# 1_1_5_Interface_board_Servos.net
KiCad netlist of a schematic drawn in Altium Designer
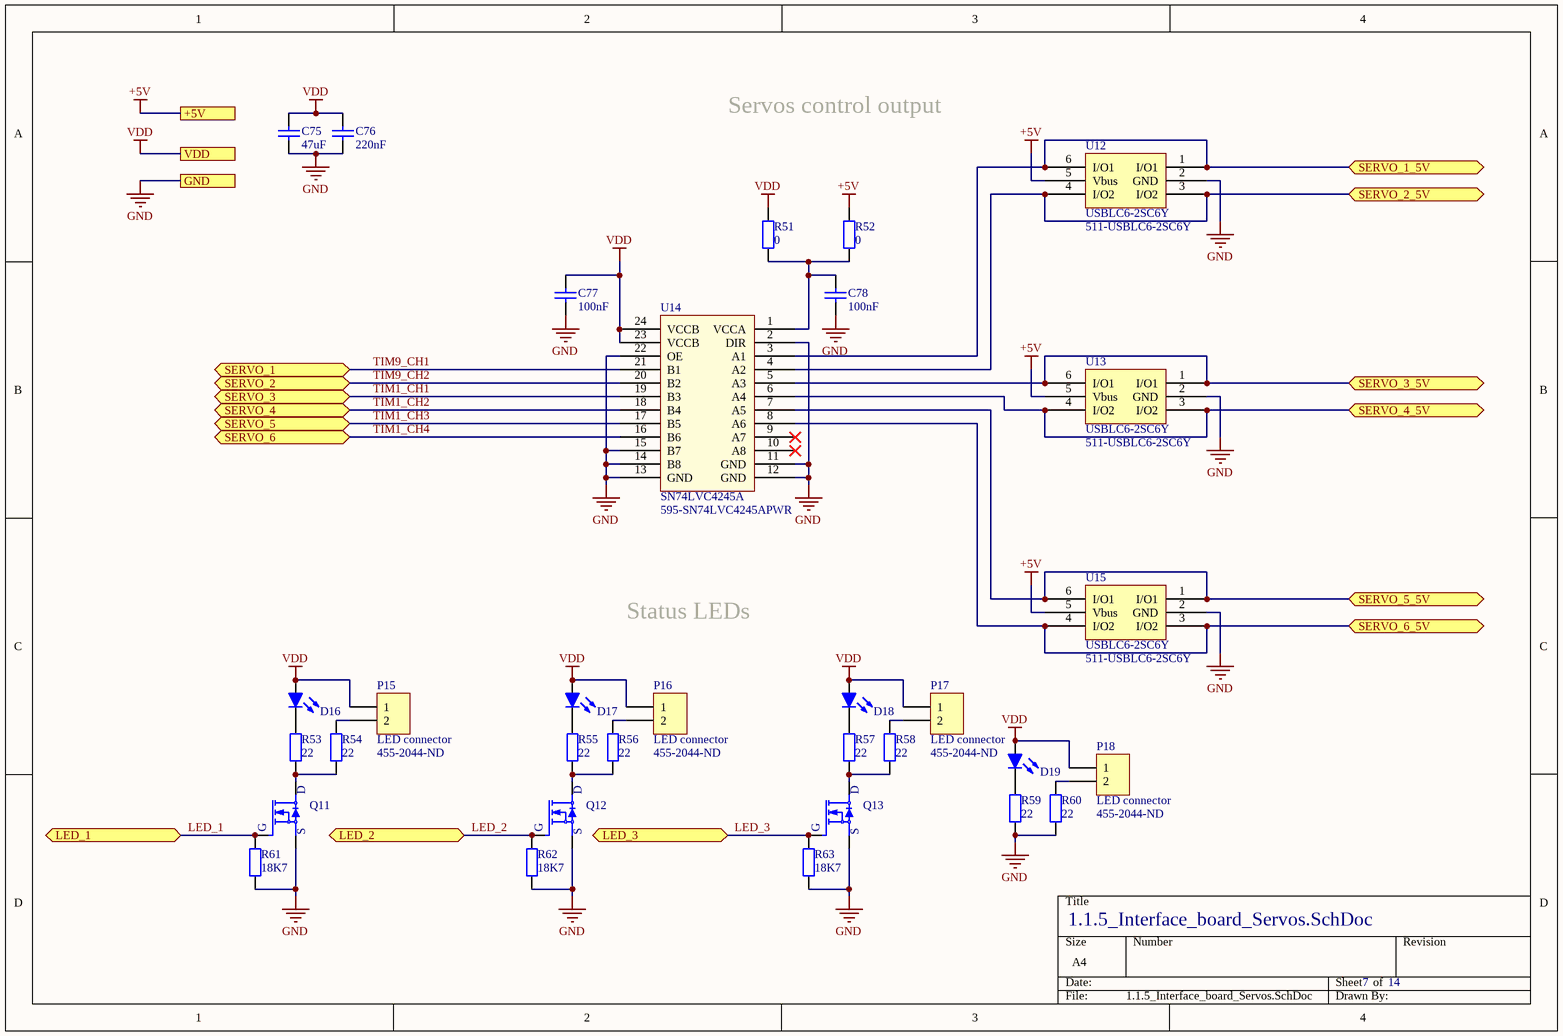
[diagram p0: 1.1.5_Interface_board_Servos.SchDoc]

(export (version "E")
  (design (tool "Eeschema 10.0.6"))
  (components
    (comp (ref "C75")
      (value "47uF")
      (footprint "CAP1206W")
      (description "Capacitor")
      (libsource (lib "Rocket_library") (part "C_47uF_25v_1206"))
    )
    (comp (ref "C76")
      (value "220nF")
      (footprint "CAP0603R")
      (description "Capacitor")
      (libsource (lib "Rocket_library") (part "C_220nF"))
    )
    (comp (ref "C77")
      (value "100nF")
      (footprint "CAP0603R")
      (description "Capacitor")
      (libsource (lib "Rocket_library") (part "C_100nF"))
    )
    (comp (ref "C78")
      (value "100nF")
      (footprint "CAP0603R")
      (description "Capacitor")
      (libsource (lib "Rocket_library") (part "C_100nF"))
    )
    (comp (ref "D16")
      (value "LED")
      (footprint "WL-SMCW")
      (description "Standard LEDs - SMD WL-SMCW Waterclr 0603 Green")
      (libsource (lib "Rocket_library") (part "LED_SMD_GREEN_0603"))
    )
    (comp (ref "D17")
      (value "LED")
      (footprint "WL-SMCW")
      (description "Standard LEDs - SMD WL-SMCW Waterclr 0603 Green")
      (libsource (lib "Rocket_library") (part "LED_SMD_GREEN_0603"))
    )
    (comp (ref "D18")
      (value "LED")
      (footprint "WL-SMCW")
      (description "Standard LEDs - SMD WL-SMCW Waterclr 0603 Green")
      (libsource (lib "Rocket_library") (part "LED_SMD_GREEN_0603"))
    )
    (comp (ref "D19")
      (value "LED")
      (footprint "WL-SMCW")
      (description "Standard LEDs - SMD WL-SMCW Waterclr 0603 Green")
      (libsource (lib "Rocket_library") (part "LED_SMD_GREEN_0603"))
    )
    (comp (ref "P15")
      (value "LED connector")
      (footprint "CON_JST_XA_ S02B-XASS-1")
      (description "Header 2p JST XA 3A right angle")
      (fields (field (name "SUPPLIER PART NUMBER 1") "455-2044-ND"))
      (libsource (lib "Rocket_library") (part "Header 2p JST XA 3A right angle"))
    )
    (comp (ref "P16")
      (value "LED connector")
      (footprint "CON_JST_XA_ S02B-XASS-1")
      (description "Header 2p JST XA 3A right angle")
      (fields (field (name "SUPPLIER PART NUMBER 1") "455-2044-ND"))
      (libsource (lib "Rocket_library") (part "Header 2p JST XA 3A right angle"))
    )
    (comp (ref "P17")
      (value "LED connector")
      (footprint "CON_JST_XA_ S02B-XASS-1")
      (description "Header 2p JST XA 3A right angle")
      (fields (field (name "SUPPLIER PART NUMBER 1") "455-2044-ND"))
      (libsource (lib "Rocket_library") (part "Header 2p JST XA 3A right angle"))
    )
    (comp (ref "P18")
      (value "LED connector")
      (footprint "CON_JST_XA_ S02B-XASS-1")
      (description "Header 2p JST XA 3A right angle")
      (fields (field (name "SUPPLIER PART NUMBER 1") "455-2044-ND"))
      (libsource (lib "Rocket_library") (part "Header 2p JST XA 3A right angle"))
    )
    (comp (ref "Q11")
      (value "MOSFET_N")
      (footprint "SOT-323-3")
      (description "MOSFET N-Ch 20V 1.4A SOT-323-3")
      (libsource (lib "Rocket_library") (part "MOSFET_N_ 20V_1.4A"))
    )
    (comp (ref "Q12")
      (value "MOSFET_N")
      (footprint "SOT-323-3")
      (description "MOSFET N-Ch 20V 1.4A SOT-323-3")
      (libsource (lib "Rocket_library") (part "MOSFET_N_ 20V_1.4A"))
    )
    (comp (ref "Q13")
      (value "MOSFET_N")
      (footprint "SOT-323-3")
      (description "MOSFET N-Ch 20V 1.4A SOT-323-3")
      (libsource (lib "Rocket_library") (part "MOSFET_N_ 20V_1.4A"))
    )
    (comp (ref "R51")
      (value "0")
      (footprint "0603")
      (description "0 Ohm")
      (libsource (lib "Rocket_library") (part "R_0603_0Ohm_jumper"))
    )
    (comp (ref "R52")
      (value "0")
      (footprint "0603")
      (description "0 Ohm")
      (libsource (lib "Rocket_library") (part "R_0603_0Ohm_jumper"))
    )
    (comp (ref "R53")
      (value "22")
      (footprint "0603")
      (description "0.25W 22Ohm")
      (libsource (lib "Rocket_library") (part "R_0603_025W_22Ohm"))
    )
    (comp (ref "R54")
      (value "22")
      (footprint "0603")
      (description "0.25W 22Ohm")
      (libsource (lib "Rocket_library") (part "R_0603_025W_22Ohm"))
    )
    (comp (ref "R55")
      (value "22")
      (footprint "0603")
      (description "0.25W 22Ohm")
      (libsource (lib "Rocket_library") (part "R_0603_025W_22Ohm"))
    )
    (comp (ref "R56")
      (value "22")
      (footprint "0603")
      (description "0.25W 22Ohm")
      (libsource (lib "Rocket_library") (part "R_0603_025W_22Ohm"))
    )
    (comp (ref "R57")
      (value "22")
      (footprint "0603")
      (description "0.25W 22Ohm")
      (libsource (lib "Rocket_library") (part "R_0603_025W_22Ohm"))
    )
    (comp (ref "R58")
      (value "22")
      (footprint "0603")
      (description "0.25W 22Ohm")
      (libsource (lib "Rocket_library") (part "R_0603_025W_22Ohm"))
    )
    (comp (ref "R59")
      (value "22")
      (footprint "0603")
      (description "0.25W 22Ohm")
      (libsource (lib "Rocket_library") (part "R_0603_025W_22Ohm"))
    )
    (comp (ref "R60")
      (value "22")
      (footprint "0603")
      (description "0.25W 22Ohm")
      (libsource (lib "Rocket_library") (part "R_0603_025W_22Ohm"))
    )
    (comp (ref "R61")
      (value "18K7")
      (footprint "0603")
      (description "0.1W 18K7")
      (libsource (lib "Rocket_library") (part "R_0603_01W_18K7"))
    )
    (comp (ref "R62")
      (value "18K7")
      (footprint "0603")
      (description "0.1W 18K7")
      (libsource (lib "Rocket_library") (part "R_0603_01W_18K7"))
    )
    (comp (ref "R63")
      (value "18K7")
      (footprint "0603")
      (description "0.1W 18K7")
      (libsource (lib "Rocket_library") (part "R_0603_01W_18K7"))
    )
    (comp (ref "U12")
      (value "USBLC6-2SC6Y")
      (footprint "SOT23-6L")
      (description "ESD Suppressors")
      (fields (field (name "SUPPLIER PART NUMBER 1") "511-USBLC6-2SC6Y"))
      (libsource (lib "Rocket_library") (part "USBLC6-2SC6Y"))
    )
    (comp (ref "U13")
      (value "USBLC6-2SC6Y")
      (footprint "SOT23-6L")
      (description "ESD Suppressors")
      (fields (field (name "SUPPLIER PART NUMBER 1") "511-USBLC6-2SC6Y"))
      (libsource (lib "Rocket_library") (part "USBLC6-2SC6Y"))
    )
    (comp (ref "U14")
      (value "SN74LVC4245A")
      (footprint "TSSOP 24")
      (description "Level shifter 8")
      (fields (field (name "SUPPLIER PART NUMBER 1") "595-SN74LVC4245APWR"))
      (libsource (lib "Rocket_library") (part "SN74LVC4245A"))
    )
    (comp (ref "U15")
      (value "USBLC6-2SC6Y")
      (footprint "SOT23-6L")
      (description "ESD Suppressors")
      (fields (field (name "SUPPLIER PART NUMBER 1") "511-USBLC6-2SC6Y"))
      (libsource (lib "Rocket_library") (part "USBLC6-2SC6Y"))
    )
  )
  (nets
    (net (code "1") (name "+5V") (class "Default")
      (node (ref "R52") (pin "2") (pinfunction "2_2") (pintype "passive"))
      (node (ref "U12") (pin "5") (pinfunction "Vbus_5") (pintype "passive"))
      (node (ref "U13") (pin "5") (pinfunction "Vbus_5") (pintype "passive"))
      (node (ref "U15") (pin "5") (pinfunction "Vbus_5") (pintype "passive"))
    )
    (net (code "2") (name "/LED_1") (class "Default")
      (node (ref "Q11") (pin "1") (pinfunction "G_1") (pintype "passive"))
      (node (ref "R61") (pin "2") (pinfunction "2_2") (pintype "passive"))
    )
    (net (code "3") (name "/LED_2") (class "Default")
      (node (ref "Q12") (pin "1") (pinfunction "G_1") (pintype "passive"))
      (node (ref "R62") (pin "2") (pinfunction "2_2") (pintype "passive"))
    )
    (net (code "4") (name "/LED_3") (class "Default")
      (node (ref "Q13") (pin "1") (pinfunction "G_1") (pintype "passive"))
      (node (ref "R63") (pin "2") (pinfunction "2_2") (pintype "passive"))
    )
    (net (code "5") (name "/SERVO_1_5V") (class "Default")
      (node (ref "U12") (pin "1") (pinfunction "I/O1_1") (pintype "passive"))
      (node (ref "U12") (pin "6") (pinfunction "I/O1_6") (pintype "passive"))
      (node (ref "U14") (pin "3") (pinfunction "A1_3") (pintype "passive"))
    )
    (net (code "6") (name "/SERVO_2_5V") (class "Default")
      (node (ref "U12") (pin "3") (pinfunction "I/O2_3") (pintype "passive"))
      (node (ref "U12") (pin "4") (pinfunction "I/O2_4") (pintype "passive"))
      (node (ref "U14") (pin "4") (pinfunction "A2_4") (pintype "passive"))
    )
    (net (code "7") (name "/SERVO_3_5V") (class "Default")
      (node (ref "U13") (pin "1") (pinfunction "I/O1_1") (pintype "passive"))
      (node (ref "U13") (pin "6") (pinfunction "I/O1_6") (pintype "passive"))
      (node (ref "U14") (pin "5") (pinfunction "A3_5") (pintype "passive"))
    )
    (net (code "8") (name "/SERVO_4_5V") (class "Default")
      (node (ref "U13") (pin "3") (pinfunction "I/O2_3") (pintype "passive"))
      (node (ref "U13") (pin "4") (pinfunction "I/O2_4") (pintype "passive"))
      (node (ref "U14") (pin "6") (pinfunction "A4_6") (pintype "passive"))
    )
    (net (code "9") (name "/SERVO_5_5V") (class "Default")
      (node (ref "U14") (pin "7") (pinfunction "A5_7") (pintype "passive"))
      (node (ref "U15") (pin "1") (pinfunction "I/O1_1") (pintype "passive"))
      (node (ref "U15") (pin "6") (pinfunction "I/O1_6") (pintype "passive"))
    )
    (net (code "10") (name "/SERVO_6_5V") (class "Default")
      (node (ref "U14") (pin "8") (pinfunction "A6_8") (pintype "passive"))
      (node (ref "U15") (pin "3") (pinfunction "I/O2_3") (pintype "passive"))
      (node (ref "U15") (pin "4") (pinfunction "I/O2_4") (pintype "passive"))
    )
    (net (code "11") (name "/TIM1_CH1") (class "Default")
      (node (ref "U14") (pin "19") (pinfunction "B3_19") (pintype "passive"))
    )
    (net (code "12") (name "/TIM1_CH2") (class "Default")
      (node (ref "U14") (pin "18") (pinfunction "B4_18") (pintype "passive"))
    )
    (net (code "13") (name "/TIM1_CH3") (class "Default")
      (node (ref "U14") (pin "17") (pinfunction "B5_17") (pintype "passive"))
    )
    (net (code "14") (name "/TIM1_CH4") (class "Default")
      (node (ref "U14") (pin "16") (pinfunction "B6_16") (pintype "passive"))
    )
    (net (code "15") (name "/TIM9_CH1") (class "Default")
      (node (ref "U14") (pin "21") (pinfunction "B1_21") (pintype "passive"))
    )
    (net (code "16") (name "/TIM9_CH2") (class "Default")
      (node (ref "U14") (pin "20") (pinfunction "B2_20") (pintype "passive"))
    )
    (net (code "17") (name "GND") (class "Default")
      (node (ref "C75") (pin "1") (pinfunction "1_1") (pintype "passive"))
      (node (ref "C76") (pin "1") (pinfunction "1_1") (pintype "passive"))
      (node (ref "C77") (pin "1") (pinfunction "1_1") (pintype "passive"))
      (node (ref "C78") (pin "1") (pinfunction "1_1") (pintype "passive"))
      (node (ref "Q11") (pin "2") (pinfunction "S_2") (pintype "passive"))
      (node (ref "Q12") (pin "2") (pinfunction "S_2") (pintype "passive"))
      (node (ref "Q13") (pin "2") (pinfunction "S_2") (pintype "passive"))
      (node (ref "R59") (pin "1") (pinfunction "1_1") (pintype "passive"))
      (node (ref "R60") (pin "1") (pinfunction "1_1") (pintype "passive"))
      (node (ref "R61") (pin "1") (pinfunction "1_1") (pintype "passive"))
      (node (ref "R62") (pin "1") (pinfunction "1_1") (pintype "passive"))
      (node (ref "R63") (pin "1") (pinfunction "1_1") (pintype "passive"))
      (node (ref "U12") (pin "2") (pinfunction "GND_2") (pintype "passive"))
      (node (ref "U13") (pin "2") (pinfunction "GND_2") (pintype "passive"))
      (node (ref "U14") (pin "11") (pinfunction "GND_11") (pintype "passive"))
      (node (ref "U14") (pin "12") (pinfunction "GND_12") (pintype "passive"))
      (node (ref "U14") (pin "13") (pinfunction "GND_13") (pintype "passive"))
      (node (ref "U14") (pin "14") (pinfunction "B8_14") (pintype "passive"))
      (node (ref "U14") (pin "15") (pinfunction "B7_15") (pintype "passive"))
      (node (ref "U14") (pin "2") (pinfunction "DIR_2") (pintype "passive"))
      (node (ref "U14") (pin "22") (pinfunction "OE_22") (pintype "passive"))
      (node (ref "U15") (pin "2") (pinfunction "GND_2") (pintype "passive"))
    )
    (net (code "18") (name "Net-(D16-PadC)") (class "Default")
      (node (ref "D16") (pin "C") (pinfunction "C_C") (pintype "passive"))
      (node (ref "R53") (pin "2") (pinfunction "2_2") (pintype "passive"))
    )
    (net (code "19") (name "Net-(D17-PadC)") (class "Default")
      (node (ref "D17") (pin "C") (pinfunction "C_C") (pintype "passive"))
      (node (ref "R55") (pin "2") (pinfunction "2_2") (pintype "passive"))
    )
    (net (code "20") (name "Net-(D18-PadC)") (class "Default")
      (node (ref "D18") (pin "C") (pinfunction "C_C") (pintype "passive"))
      (node (ref "R57") (pin "2") (pinfunction "2_2") (pintype "passive"))
    )
    (net (code "21") (name "Net-(D19-PadC)") (class "Default")
      (node (ref "D19") (pin "C") (pinfunction "C_C") (pintype "passive"))
      (node (ref "R59") (pin "2") (pinfunction "2_2") (pintype "passive"))
    )
    (net (code "22") (name "Net-(P15-Pad2)") (class "Default")
      (node (ref "P15") (pin "2") (pinfunction "2_2") (pintype "passive"))
      (node (ref "R54") (pin "2") (pinfunction "2_2") (pintype "passive"))
    )
    (net (code "23") (name "Net-(P16-Pad2)") (class "Default")
      (node (ref "P16") (pin "2") (pinfunction "2_2") (pintype "passive"))
      (node (ref "R56") (pin "2") (pinfunction "2_2") (pintype "passive"))
    )
    (net (code "24") (name "Net-(P17-Pad2)") (class "Default")
      (node (ref "P17") (pin "2") (pinfunction "2_2") (pintype "passive"))
      (node (ref "R58") (pin "2") (pinfunction "2_2") (pintype "passive"))
    )
    (net (code "25") (name "Net-(P18-Pad2)") (class "Default")
      (node (ref "P18") (pin "2") (pinfunction "2_2") (pintype "passive"))
      (node (ref "R60") (pin "2") (pinfunction "2_2") (pintype "passive"))
    )
    (net (code "26") (name "Net-(Q11-D)") (class "Default")
      (node (ref "Q11") (pin "3") (pinfunction "D_3") (pintype "passive"))
      (node (ref "R53") (pin "1") (pinfunction "1_1") (pintype "passive"))
      (node (ref "R54") (pin "1") (pinfunction "1_1") (pintype "passive"))
    )
    (net (code "27") (name "Net-(Q12-D)") (class "Default")
      (node (ref "Q12") (pin "3") (pinfunction "D_3") (pintype "passive"))
      (node (ref "R55") (pin "1") (pinfunction "1_1") (pintype "passive"))
      (node (ref "R56") (pin "1") (pinfunction "1_1") (pintype "passive"))
    )
    (net (code "28") (name "Net-(Q13-D)") (class "Default")
      (node (ref "Q13") (pin "3") (pinfunction "D_3") (pintype "passive"))
      (node (ref "R57") (pin "1") (pinfunction "1_1") (pintype "passive"))
      (node (ref "R58") (pin "1") (pinfunction "1_1") (pintype "passive"))
    )
    (net (code "29") (name "Net-(U14-VCCA)") (class "Default")
      (node (ref "C78") (pin "2") (pinfunction "2_2") (pintype "passive"))
      (node (ref "R51") (pin "1") (pinfunction "1_1") (pintype "passive"))
      (node (ref "R52") (pin "1") (pinfunction "1_1") (pintype "passive"))
      (node (ref "U14") (pin "1") (pinfunction "VCCA_1") (pintype "passive"))
    )
    (net (code "30") (name "VDD") (class "Default")
      (node (ref "C75") (pin "2") (pinfunction "2_2") (pintype "passive"))
      (node (ref "C76") (pin "2") (pinfunction "2_2") (pintype "passive"))
      (node (ref "C77") (pin "2") (pinfunction "2_2") (pintype "passive"))
      (node (ref "D16") (pin "A") (pinfunction "A_A") (pintype "passive"))
      (node (ref "D17") (pin "A") (pinfunction "A_A") (pintype "passive"))
      (node (ref "D18") (pin "A") (pinfunction "A_A") (pintype "passive"))
      (node (ref "D19") (pin "A") (pinfunction "A_A") (pintype "passive"))
      (node (ref "P15") (pin "1") (pinfunction "1_1") (pintype "passive"))
      (node (ref "P16") (pin "1") (pinfunction "1_1") (pintype "passive"))
      (node (ref "P17") (pin "1") (pinfunction "1_1") (pintype "passive"))
      (node (ref "P18") (pin "1") (pinfunction "1_1") (pintype "passive"))
      (node (ref "R51") (pin "2") (pinfunction "2_2") (pintype "passive"))
      (node (ref "U14") (pin "23") (pinfunction "VCCB_23") (pintype "passive"))
      (node (ref "U14") (pin "24") (pinfunction "VCCB_24") (pintype "passive"))
    )
    (net (code "31") (name "unconnected-(U14-A7-Pad9)") (class "Default")
      (node (ref "U14") (pin "9") (pinfunction "A7_9") (pintype "passive+no_connect"))
    )
    (net (code "32") (name "unconnected-(U14-A8-Pad10)") (class "Default")
      (node (ref "U14") (pin "10") (pinfunction "A8_10") (pintype "passive+no_connect"))
    )
  )
)
